# P20_WIFI_BT_SDIO_IO_EXPANDERS.net
KiCad netlist of a schematic drawn in Altium Designer
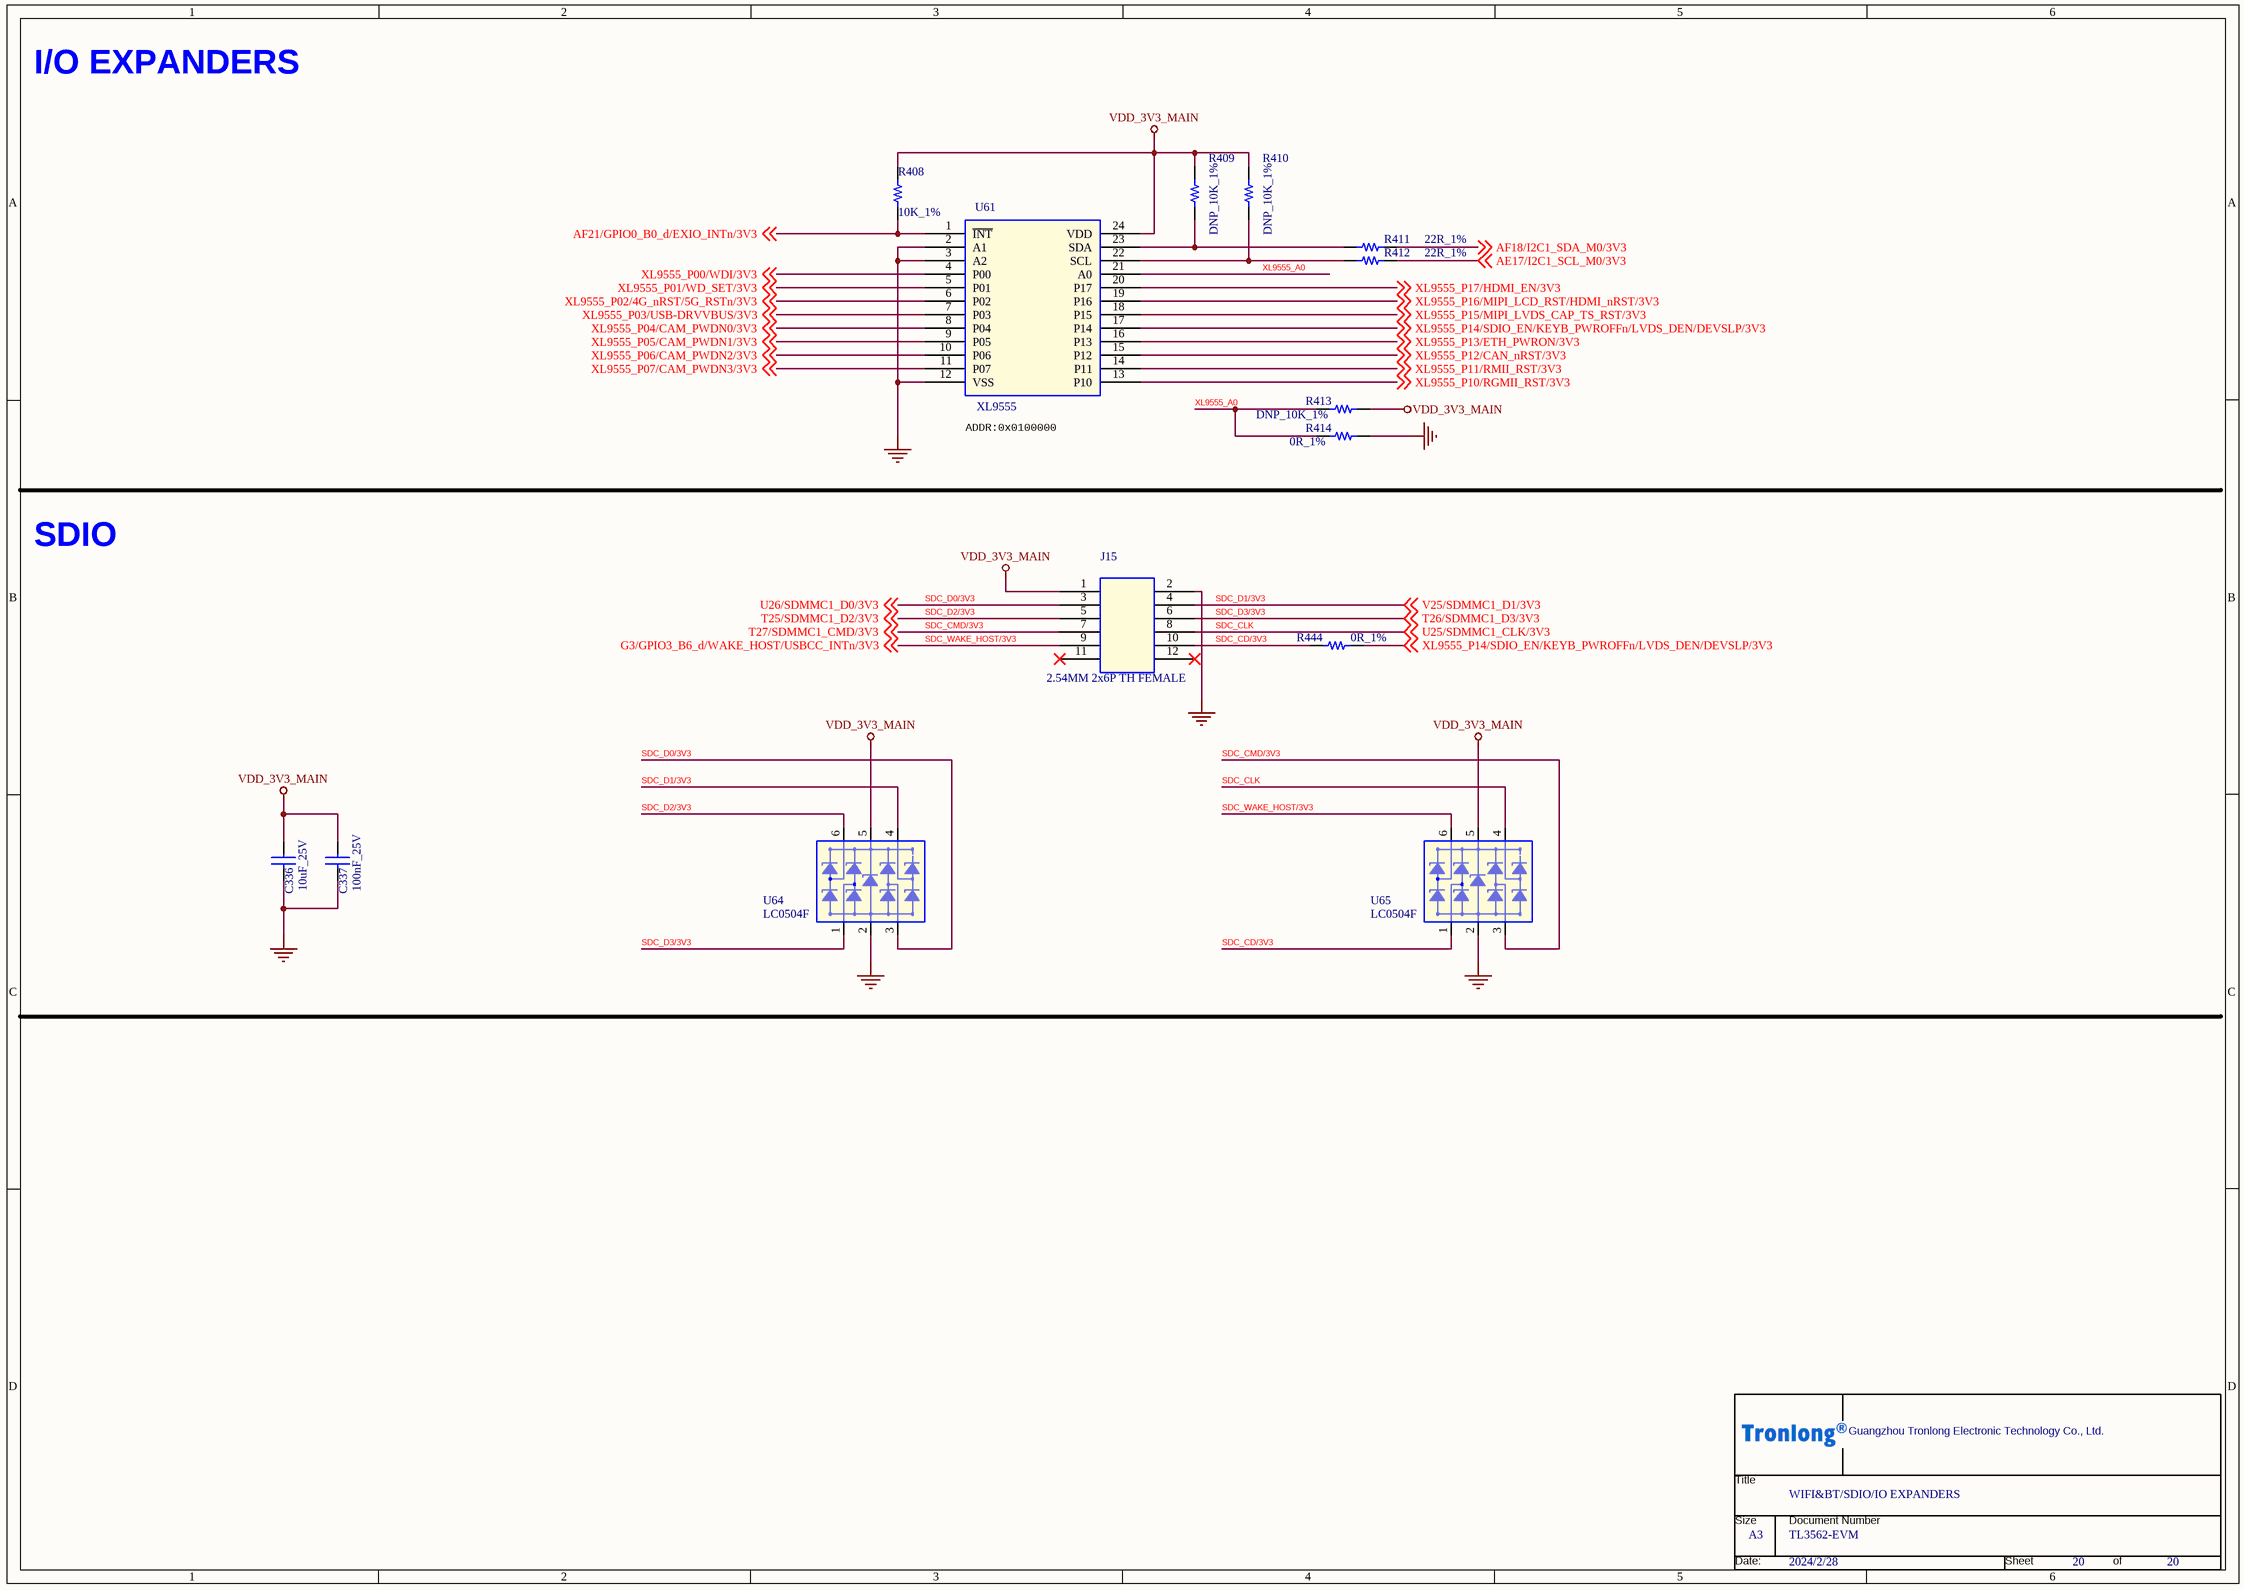
[diagram p0: P20_WIFI&BT_SDIO_IO EXPANDERS.SchDoc]

(export (version "E")
  (design (tool "Eeschema 10.0.6"))
  (components
    (comp (ref "C336")
      (value "10uF_25V")
      (footprint "C0603")
      (description "贴片陶瓷电容,10uF,10%,10V,X5R")
      (libsource (lib "*") (part "CAP NP_Dup3"))
    )
    (comp (ref "C337")
      (value "100nF_25V")
      (footprint "C0402")
      (description "贴片陶瓷电容,100nF,10%,25V,X5R")
      (libsource (lib "*") (part "CAP NP_Dup3"))
    )
    (comp (ref "J15")
      (value "2.54MM 2x6P TH FEMALE")
      (footprint "header_2x6_2d54_male")
      (description "排母,2X6PIN,间距2.54MM,180度,插件")
      (fields
        (field (name "MANUFACTURER") "深圳市长江连接器有限公司（CJT）")
        (field (name "MANUFACTURER PARTNUMBER") "A2541HWV-2x6P")
      )
      (libsource (lib "*") (part "CON12A"))
    )
    (comp (ref "R408")
      (value "10K_1%")
      (footprint "R0402")
      (description "贴片电阻,10K,±1%,1/16W")
      (libsource (lib "*") (part "Resistor_Dup1"))
    )
    (comp (ref "R409")
      (value "DNP_10K_1%")
      (footprint "R0402")
      (description "贴片电阻,10K,±1%,1/16W")
      (libsource (lib "*") (part "Resistor_Dup1"))
    )
    (comp (ref "R410")
      (value "DNP_10K_1%")
      (footprint "R0402")
      (description "贴片电阻,10K,±1%,1/16W")
      (libsource (lib "*") (part "Resistor_Dup1"))
    )
    (comp (ref "R411")
      (value "22R_1%")
      (footprint "R0402")
      (description "贴片电阻,22R,±1%,1/16W")
      (libsource (lib "*") (part "Resistor_Dup1"))
    )
    (comp (ref "R412")
      (value "22R_1%")
      (footprint "R0402")
      (description "贴片电阻,22R,±1%,1/16W")
      (libsource (lib "*") (part "Resistor_Dup1"))
    )
    (comp (ref "R413")
      (value "DNP_10K_1%")
      (footprint "R0402")
      (description "贴片电阻,10K,±1%,1/16W")
      (libsource (lib "*") (part "Resistor_Dup1"))
    )
    (comp (ref "R414")
      (value "0R_1%")
      (footprint "R0603")
      (description "贴片电阻,0R,±1%,1/10W")
      (libsource (lib "*") (part "Resistor_Dup1"))
    )
    (comp (ref "R444")
      (value "0R_1%")
      (footprint "R0402")
      (description "贴片电阻,0R,±1%,1/16W")
      (libsource (lib "*") (part "Resistor_Dup3"))
    )
    (comp (ref "U61")
      (value "XL9555")
      (footprint "TSSOP24")
      (description "拓展IO芯片")
      (fields (field (name "MANUFACTURER") "信路达信息技术（厦门）有限公司（xinluda）"))
      (libsource (lib "*") (part "XL9555_0"))
    )
    (comp (ref "U64")
      (value "LC0504F")
      (footprint "SOT363")
      (description "ESD二极管,VRWM=5V,VBR=6V,四组,单向,8KV,15KV")
      (fields
        (field (name "MANUFACTURER PART NUMBER") "PRTR5V0U4Y")
        (field (name "MANUFACTURER") "上海雷卯电子科技有限公司（Leiditech）")
      )
      (libsource (lib "*") (part "PRTR5V0U4Y_0"))
    )
    (comp (ref "U65")
      (value "LC0504F")
      (footprint "SOT363")
      (description "ESD二极管,VRWM=5V,VBR=6V,四组,单向,8KV,15KV")
      (fields
        (field (name "MANUFACTURER") "上海雷卯电子科技有限公司（Leiditech）")
        (field (name "MANUFACTURER PART NUMBER") "PRTR5V0U4Y")
      )
      (libsource (lib "*") (part "PRTR5V0U4Y_0"))
    )
  )
  (nets
    (net (code "1") (name "/SDC_CD{slash}3V3") (class "Default")
      (node (ref "J15") (pin "10") (pinfunction "10_10") (pintype "passive"))
      (node (ref "R444") (pin "2") (pinfunction "2_2") (pintype "passive"))
      (node (ref "U65") (pin "1") (pinfunction "1_1") (pintype "passive"))
    )
    (net (code "2") (name "/XL9555_A0") (class "Default")
      (node (ref "R413") (pin "2") (pinfunction "2_2") (pintype "passive"))
      (node (ref "R414") (pin "1") (pinfunction "1_1") (pintype "passive"))
      (node (ref "U61") (pin "21") (pinfunction "A0_21") (pintype "passive"))
    )
    (net (code "3") (name "AE17{slash}I2C1_SCL_M0{slash}3V3") (class "Default")
      (node (ref "R412") (pin "1") (pinfunction "1_1") (pintype "passive"))
    )
    (net (code "4") (name "AF18{slash}I2C1_SDA_M0{slash}3V3") (class "Default")
      (node (ref "R411") (pin "1") (pinfunction "1_1") (pintype "passive"))
    )
    (net (code "5") (name "AF21{slash}GPIO0_B0_d{slash}EXIO_INTn{slash}3V3") (class "Default")
      (node (ref "R408") (pin "2") (pinfunction "2_2") (pintype "passive"))
      (node (ref "U61") (pin "1") (pinfunction "~{INT}_1") (pintype "passive"))
    )
    (net (code "6") (name "G3{slash}GPIO3_B6_d{slash}WAKE_HOST{slash}USBCC_INTn{slash}3V3") (class "Default")
      (node (ref "J15") (pin "9") (pinfunction "9_9") (pintype "passive"))
      (node (ref "U65") (pin "6") (pinfunction "6_6") (pintype "passive"))
    )
    (net (code "7") (name "GND") (class "Default")
      (node (ref "C336") (pin "2") (pinfunction "2_2") (pintype "passive"))
      (node (ref "C337") (pin "2") (pinfunction "2_2") (pintype "passive"))
      (node (ref "J15") (pin "2") (pinfunction "2_2") (pintype "passive"))
      (node (ref "R414") (pin "2") (pinfunction "2_2") (pintype "passive"))
      (node (ref "U61") (pin "12") (pinfunction "VSS_12") (pintype "passive"))
      (node (ref "U61") (pin "2") (pinfunction "A1_2") (pintype "passive"))
      (node (ref "U61") (pin "3") (pinfunction "A2_3") (pintype "passive"))
      (node (ref "U64") (pin "2") (pinfunction "2_2") (pintype "passive"))
      (node (ref "U65") (pin "2") (pinfunction "2_2") (pintype "passive"))
    )
    (net (code "8") (name "Net-(U61-SCL)") (class "Default")
      (node (ref "R410") (pin "2") (pinfunction "2_2") (pintype "passive"))
      (node (ref "R412") (pin "2") (pinfunction "2_2") (pintype "passive"))
      (node (ref "U61") (pin "22") (pinfunction "SCL_22") (pintype "passive"))
    )
    (net (code "9") (name "Net-(U61-SDA)") (class "Default")
      (node (ref "R409") (pin "2") (pinfunction "2_2") (pintype "passive"))
      (node (ref "R411") (pin "2") (pinfunction "2_2") (pintype "passive"))
      (node (ref "U61") (pin "23") (pinfunction "SDA_23") (pintype "passive"))
    )
    (net (code "10") (name "T25{slash}SDMMC1_D2{slash}3V3") (class "Default")
      (node (ref "J15") (pin "5") (pinfunction "5_5") (pintype "passive"))
      (node (ref "U64") (pin "6") (pinfunction "6_6") (pintype "passive"))
    )
    (net (code "11") (name "T26{slash}SDMMC1_D3{slash}3V3") (class "Default")
      (node (ref "J15") (pin "6") (pinfunction "6_6") (pintype "passive"))
      (node (ref "U64") (pin "1") (pinfunction "1_1") (pintype "passive"))
    )
    (net (code "12") (name "T27{slash}SDMMC1_CMD{slash}3V3") (class "Default")
      (node (ref "J15") (pin "7") (pinfunction "7_7") (pintype "passive"))
      (node (ref "U65") (pin "3") (pinfunction "3_3") (pintype "passive"))
    )
    (net (code "13") (name "U25{slash}SDMMC1_CLK{slash}3V3") (class "Default")
      (node (ref "J15") (pin "8") (pinfunction "8_8") (pintype "passive"))
      (node (ref "U65") (pin "4") (pinfunction "4_4") (pintype "passive"))
    )
    (net (code "14") (name "U26{slash}SDMMC1_D0{slash}3V3") (class "Default")
      (node (ref "J15") (pin "3") (pinfunction "3_3") (pintype "passive"))
      (node (ref "U64") (pin "3") (pinfunction "3_3") (pintype "passive"))
    )
    (net (code "15") (name "V25{slash}SDMMC1_D1{slash}3V3") (class "Default")
      (node (ref "J15") (pin "4") (pinfunction "4_4") (pintype "passive"))
      (node (ref "U64") (pin "4") (pinfunction "4_4") (pintype "passive"))
    )
    (net (code "16") (name "VDD_3V3_MAIN") (class "Default")
      (node (ref "C336") (pin "1") (pinfunction "1_1") (pintype "passive"))
      (node (ref "C337") (pin "1") (pinfunction "1_1") (pintype "passive"))
      (node (ref "J15") (pin "1") (pinfunction "1_1") (pintype "passive"))
      (node (ref "R408") (pin "1") (pinfunction "1_1") (pintype "passive"))
      (node (ref "R409") (pin "1") (pinfunction "1_1") (pintype "passive"))
      (node (ref "R410") (pin "1") (pinfunction "1_1") (pintype "passive"))
      (node (ref "R413") (pin "1") (pinfunction "1_1") (pintype "passive"))
      (node (ref "U61") (pin "24") (pinfunction "VDD_24") (pintype "passive"))
      (node (ref "U64") (pin "5") (pinfunction "5_5") (pintype "passive"))
      (node (ref "U65") (pin "5") (pinfunction "5_5") (pintype "passive"))
    )
    (net (code "17") (name "XL9555_P00{slash}WDI{slash}3V3") (class "Default")
      (node (ref "U61") (pin "4") (pinfunction "P00_4") (pintype "passive"))
    )
    (net (code "18") (name "XL9555_P01{slash}WD_SET{slash}3V3") (class "Default")
      (node (ref "U61") (pin "5") (pinfunction "P01_5") (pintype "passive"))
    )
    (net (code "19") (name "XL9555_P02{slash}4G_nRST{slash}5G_RSTn{slash}3V3") (class "Default")
      (node (ref "U61") (pin "6") (pinfunction "P02_6") (pintype "passive"))
    )
    (net (code "20") (name "XL9555_P03{slash}USB-DRVVBUS{slash}3V3") (class "Default")
      (node (ref "U61") (pin "7") (pinfunction "P03_7") (pintype "passive"))
    )
    (net (code "21") (name "XL9555_P04{slash}CAM_PWDN0{slash}3V3") (class "Default")
      (node (ref "U61") (pin "8") (pinfunction "P04_8") (pintype "passive"))
    )
    (net (code "22") (name "XL9555_P05{slash}CAM_PWDN1{slash}3V3") (class "Default")
      (node (ref "U61") (pin "9") (pinfunction "P05_9") (pintype "passive"))
    )
    (net (code "23") (name "XL9555_P06{slash}CAM_PWDN2{slash}3V3") (class "Default")
      (node (ref "U61") (pin "10") (pinfunction "P06_10") (pintype "passive"))
    )
    (net (code "24") (name "XL9555_P07{slash}CAM_PWDN3{slash}3V3") (class "Default")
      (node (ref "U61") (pin "11") (pinfunction "P07_11") (pintype "passive"))
    )
    (net (code "25") (name "XL9555_P10{slash}RGMII_RST{slash}3V3") (class "Default")
      (node (ref "U61") (pin "13") (pinfunction "P10_13") (pintype "passive"))
    )
    (net (code "26") (name "XL9555_P11{slash}RMII_RST{slash}3V3") (class "Default")
      (node (ref "U61") (pin "14") (pinfunction "P11_14") (pintype "passive"))
    )
    (net (code "27") (name "XL9555_P12{slash}CAN_nRST{slash}3V3") (class "Default")
      (node (ref "U61") (pin "15") (pinfunction "P12_15") (pintype "passive"))
    )
    (net (code "28") (name "XL9555_P13{slash}ETH_PWRON{slash}3V3") (class "Default")
      (node (ref "U61") (pin "16") (pinfunction "P13_16") (pintype "passive"))
    )
    (net (code "29") (name "XL9555_P14{slash}SDIO_EN{slash}KEYB_PWROFFn{slash}LVDS_DEN{slash}DEVSLP{slash}3V3") (class "Default")
      (node (ref "R444") (pin "1") (pinfunction "1_1") (pintype "passive"))
      (node (ref "U61") (pin "17") (pinfunction "P14_17") (pintype "passive"))
    )
    (net (code "30") (name "XL9555_P15{slash}MIPI_LVDS_CAP_TS_RST{slash}3V3") (class "Default")
      (node (ref "U61") (pin "18") (pinfunction "P15_18") (pintype "passive"))
    )
    (net (code "31") (name "XL9555_P16{slash}MIPI_LCD_RST{slash}HDMI_nRST{slash}3V3") (class "Default")
      (node (ref "U61") (pin "19") (pinfunction "P16_19") (pintype "passive"))
    )
    (net (code "32") (name "XL9555_P17{slash}HDMI_EN{slash}3V3") (class "Default")
      (node (ref "U61") (pin "20") (pinfunction "P17_20") (pintype "passive"))
    )
    (net (code "33") (name "unconnected-(J15-Pad11)") (class "Default")
      (node (ref "J15") (pin "11") (pinfunction "11_11") (pintype "passive+no_connect"))
    )
    (net (code "34") (name "unconnected-(J15-Pad12)") (class "Default")
      (node (ref "J15") (pin "12") (pinfunction "12_12") (pintype "passive+no_connect"))
    )
  )
)
